# AATB-V2_1.net
KiCad netlist of a schematic drawn in Altium Designer
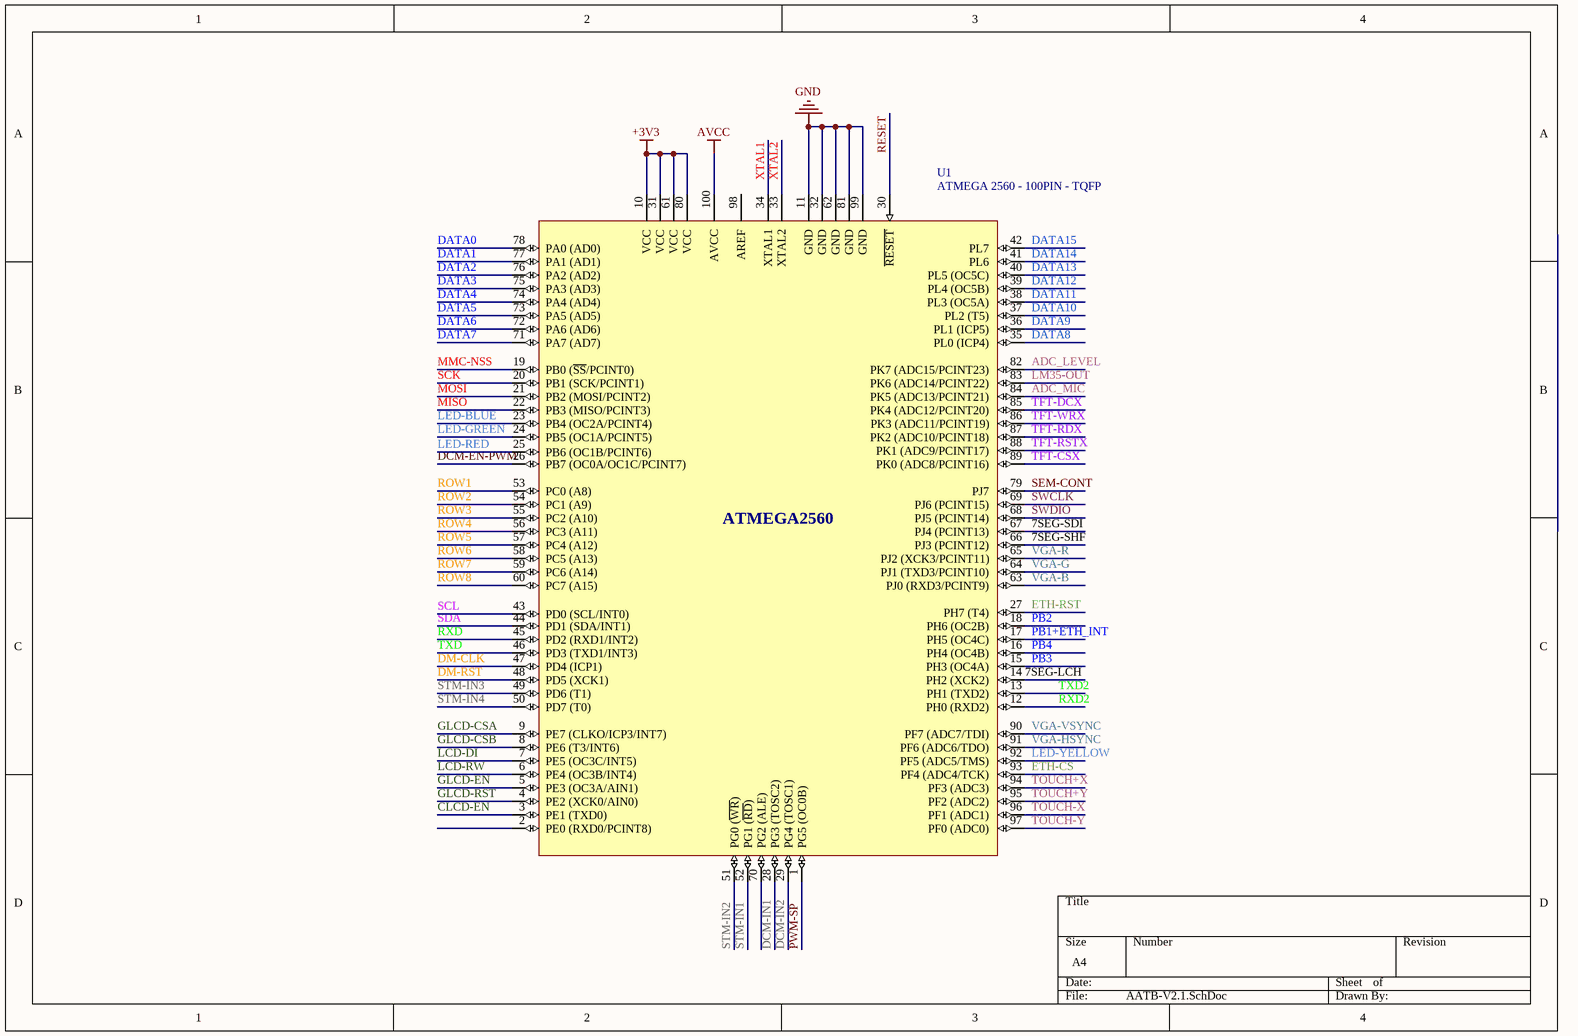
[diagram p0: AATB-V2.1.SchDoc]

(export (version "E")
  (design (tool "Eeschema 10.0.6"))
  (components
    (comp (ref "U1")
      (value "ATMEGA 2560 - 100PIN - TQFP")
      (footprint "cpu-100-26")
      (libsource (lib "Tl494") (part "ATMEGA 2560"))
    )
  )
  (nets
    (net (code "1") (name "+3V3") (class "Default")
      (node (ref "U1") (pin "10") (pinfunction "VCC_10") (pintype "power_in"))
      (node (ref "U1") (pin "31") (pinfunction "VCC_31") (pintype "power_in"))
      (node (ref "U1") (pin "61") (pinfunction "VCC_61") (pintype "power_in"))
      (node (ref "U1") (pin "80") (pinfunction "VCC_80") (pintype "power_in"))
    )
    (net (code "2") (name "/7SEG-LCH") (class "Default")
      (node (ref "U1") (pin "14") (pinfunction "PH2_(XCK2)_14") (pintype "bidirectional"))
    )
    (net (code "3") (name "/7SEG-SDI") (class "Default")
      (node (ref "U1") (pin "67") (pinfunction "PJ4_(PCINT13)_67") (pintype "bidirectional"))
    )
    (net (code "4") (name "/7SEG-SHF") (class "Default")
      (node (ref "U1") (pin "66") (pinfunction "PJ3_(PCINT12)_66") (pintype "bidirectional"))
    )
    (net (code "5") (name "/ADC_LEVEL") (class "Default")
      (node (ref "U1") (pin "82") (pinfunction "PK7_(ADC15/PCINT23)_82") (pintype "bidirectional"))
    )
    (net (code "6") (name "/ADC_MIC") (class "Default")
      (node (ref "U1") (pin "84") (pinfunction "PK5_(ADC13/PCINT21)_84") (pintype "bidirectional"))
    )
    (net (code "7") (name "/CLCD-EN") (class "Default")
      (node (ref "U1") (pin "3") (pinfunction "PE1_(TXD0)_3") (pintype "bidirectional"))
    )
    (net (code "8") (name "/DATA0") (class "Default")
      (node (ref "U1") (pin "78") (pinfunction "PA0_(AD0)_78") (pintype "bidirectional"))
    )
    (net (code "9") (name "/DATA1") (class "Default")
      (node (ref "U1") (pin "77") (pinfunction "PA1_(AD1)_77") (pintype "bidirectional"))
    )
    (net (code "10") (name "/DATA2") (class "Default")
      (node (ref "U1") (pin "76") (pinfunction "PA2_(AD2)_76") (pintype "bidirectional"))
    )
    (net (code "11") (name "/DATA3") (class "Default")
      (node (ref "U1") (pin "75") (pinfunction "PA3_(AD3)_75") (pintype "bidirectional"))
    )
    (net (code "12") (name "/DATA4") (class "Default")
      (node (ref "U1") (pin "74") (pinfunction "PA4_(AD4)_74") (pintype "bidirectional"))
    )
    (net (code "13") (name "/DATA5") (class "Default")
      (node (ref "U1") (pin "73") (pinfunction "PA5_(AD5)_73") (pintype "bidirectional"))
    )
    (net (code "14") (name "/DATA6") (class "Default")
      (node (ref "U1") (pin "72") (pinfunction "PA6_(AD6)_72") (pintype "bidirectional"))
    )
    (net (code "15") (name "/DATA7") (class "Default")
      (node (ref "U1") (pin "71") (pinfunction "PA7_(AD7)_71") (pintype "bidirectional"))
    )
    (net (code "16") (name "/DATA8") (class "Default")
      (node (ref "U1") (pin "35") (pinfunction "PL0_(ICP4)_35") (pintype "bidirectional"))
    )
    (net (code "17") (name "/DATA9") (class "Default")
      (node (ref "U1") (pin "36") (pinfunction "PL1_(ICP5)_36") (pintype "bidirectional"))
    )
    (net (code "18") (name "/DATA10") (class "Default")
      (node (ref "U1") (pin "37") (pinfunction "PL2_(T5)_37") (pintype "bidirectional"))
    )
    (net (code "19") (name "/DATA11") (class "Default")
      (node (ref "U1") (pin "38") (pinfunction "PL3_(OC5A)_38") (pintype "bidirectional"))
    )
    (net (code "20") (name "/DATA12") (class "Default")
      (node (ref "U1") (pin "39") (pinfunction "PL4_(OC5B)_39") (pintype "bidirectional"))
    )
    (net (code "21") (name "/DATA13") (class "Default")
      (node (ref "U1") (pin "40") (pinfunction "PL5_(OC5C)_40") (pintype "bidirectional"))
    )
    (net (code "22") (name "/DATA14") (class "Default")
      (node (ref "U1") (pin "41") (pinfunction "PL6_41") (pintype "bidirectional"))
    )
    (net (code "23") (name "/DATA15") (class "Default")
      (node (ref "U1") (pin "42") (pinfunction "PL7_42") (pintype "bidirectional"))
    )
    (net (code "24") (name "/DCM-EN-PWM") (class "Default")
      (node (ref "U1") (pin "26") (pinfunction "PB7_(OC0A/OC1C/PCINT7)_26") (pintype "bidirectional"))
    )
    (net (code "25") (name "/DCM-IN1") (class "Default")
      (node (ref "U1") (pin "28") (pinfunction "PG3_(TOSC2)_28") (pintype "bidirectional"))
    )
    (net (code "26") (name "/DCM-IN2") (class "Default")
      (node (ref "U1") (pin "29") (pinfunction "PG4_(TOSC1)_29") (pintype "bidirectional"))
    )
    (net (code "27") (name "/DM-CLK") (class "Default")
      (node (ref "U1") (pin "47") (pinfunction "PD4_(ICP1)_47") (pintype "bidirectional"))
    )
    (net (code "28") (name "/DM-RST") (class "Default")
      (node (ref "U1") (pin "48") (pinfunction "PD5_(XCK1)_48") (pintype "bidirectional"))
    )
    (net (code "29") (name "/ETH-CS") (class "Default")
      (node (ref "U1") (pin "93") (pinfunction "PF4_(ADC4/TCK)_93") (pintype "bidirectional"))
    )
    (net (code "30") (name "/ETH-RST") (class "Default")
      (node (ref "U1") (pin "27") (pinfunction "PH7_(T4)_27") (pintype "bidirectional"))
    )
    (net (code "31") (name "/GLCD-CSA") (class "Default")
      (node (ref "U1") (pin "9") (pinfunction "PE7_(CLKO/ICP3/INT7)_9") (pintype "bidirectional"))
    )
    (net (code "32") (name "/GLCD-CSB") (class "Default")
      (node (ref "U1") (pin "8") (pinfunction "PE6_(T3/INT6)_8") (pintype "bidirectional"))
    )
    (net (code "33") (name "/GLCD-EN") (class "Default")
      (node (ref "U1") (pin "5") (pinfunction "PE3_(OC3A/AIN1)_5") (pintype "bidirectional"))
    )
    (net (code "34") (name "/GLCD-RST") (class "Default")
      (node (ref "U1") (pin "4") (pinfunction "PE2_(XCK0/AIN0)_4") (pintype "bidirectional"))
    )
    (net (code "35") (name "/LCD-DI") (class "Default")
      (node (ref "U1") (pin "7") (pinfunction "PE5_(OC3C/INT5)_7") (pintype "bidirectional"))
    )
    (net (code "36") (name "/LCD-RW") (class "Default")
      (node (ref "U1") (pin "6") (pinfunction "PE4_(OC3B/INT4)_6") (pintype "bidirectional"))
    )
    (net (code "37") (name "/LED-BLUE") (class "Default")
      (node (ref "U1") (pin "23") (pinfunction "PB4_(OC2A/PCINT4)_23") (pintype "bidirectional"))
    )
    (net (code "38") (name "/LED-GREEN") (class "Default")
      (node (ref "U1") (pin "24") (pinfunction "PB5_(OC1A/PCINT5)_24") (pintype "bidirectional"))
    )
    (net (code "39") (name "/LED-RED") (class "Default")
      (node (ref "U1") (pin "25") (pinfunction "PB6_(OC1B/PCINT6)_25") (pintype "bidirectional"))
    )
    (net (code "40") (name "/LED-YELLOW") (class "Default")
      (node (ref "U1") (pin "92") (pinfunction "PF5_(ADC5/TMS)_92") (pintype "bidirectional"))
    )
    (net (code "41") (name "/LM35-OUT") (class "Default")
      (node (ref "U1") (pin "83") (pinfunction "PK6_(ADC14/PCINT22)_83") (pintype "bidirectional"))
    )
    (net (code "42") (name "/MISO") (class "Default")
      (node (ref "U1") (pin "22") (pinfunction "PB3_(MISO/PCINT3)_22") (pintype "bidirectional"))
    )
    (net (code "43") (name "/MMC-NSS") (class "Default")
      (node (ref "U1") (pin "19") (pinfunction "PB0_(~{SS}/PCINT0)_19") (pintype "bidirectional"))
    )
    (net (code "44") (name "/MOSI") (class "Default")
      (node (ref "U1") (pin "21") (pinfunction "PB2_(MOSI/PCINT2)_21") (pintype "bidirectional"))
    )
    (net (code "45") (name "/PB1+ETH_INT") (class "Default")
      (node (ref "U1") (pin "17") (pinfunction "PH5_(OC4C)_17") (pintype "bidirectional"))
    )
    (net (code "46") (name "/PB2") (class "Default")
      (node (ref "U1") (pin "18") (pinfunction "PH6_(OC2B)_18") (pintype "bidirectional"))
    )
    (net (code "47") (name "/PB3") (class "Default")
      (node (ref "U1") (pin "15") (pinfunction "PH3_(OC4A)_15") (pintype "bidirectional"))
    )
    (net (code "48") (name "/PB4") (class "Default")
      (node (ref "U1") (pin "16") (pinfunction "PH4_(OC4B)_16") (pintype "bidirectional"))
    )
    (net (code "49") (name "/PWM-SP") (class "Default")
      (node (ref "U1") (pin "1") (pinfunction "PG5_(OC0B)_1") (pintype "bidirectional"))
    )
    (net (code "50") (name "/RESET") (class "Default")
      (node (ref "U1") (pin "30") (pinfunction "~{RESET}_30") (pintype "input"))
    )
    (net (code "51") (name "/ROW1") (class "Default")
      (node (ref "U1") (pin "53") (pinfunction "PC0_(A8)_53") (pintype "bidirectional"))
    )
    (net (code "52") (name "/ROW2") (class "Default")
      (node (ref "U1") (pin "54") (pinfunction "PC1_(A9)_54") (pintype "bidirectional"))
    )
    (net (code "53") (name "/ROW3") (class "Default")
      (node (ref "U1") (pin "55") (pinfunction "PC2_(A10)_55") (pintype "bidirectional"))
    )
    (net (code "54") (name "/ROW4") (class "Default")
      (node (ref "U1") (pin "56") (pinfunction "PC3_(A11)_56") (pintype "bidirectional"))
    )
    (net (code "55") (name "/ROW5") (class "Default")
      (node (ref "U1") (pin "57") (pinfunction "PC4_(A12)_57") (pintype "bidirectional"))
    )
    (net (code "56") (name "/ROW6") (class "Default")
      (node (ref "U1") (pin "58") (pinfunction "PC5_(A13)_58") (pintype "bidirectional"))
    )
    (net (code "57") (name "/ROW7") (class "Default")
      (node (ref "U1") (pin "59") (pinfunction "PC6_(A14)_59") (pintype "bidirectional"))
    )
    (net (code "58") (name "/ROW8") (class "Default")
      (node (ref "U1") (pin "60") (pinfunction "PC7_(A15)_60") (pintype "bidirectional"))
    )
    (net (code "59") (name "/RXD") (class "Default")
      (node (ref "U1") (pin "45") (pinfunction "PD2_(RXD1/INT2)_45") (pintype "bidirectional"))
    )
    (net (code "60") (name "/RXD2") (class "Default")
      (node (ref "U1") (pin "12") (pinfunction "PH0_(RXD2)_12") (pintype "bidirectional"))
    )
    (net (code "61") (name "/SCK") (class "Default")
      (node (ref "U1") (pin "20") (pinfunction "PB1_(SCK/PCINT1)_20") (pintype "bidirectional"))
    )
    (net (code "62") (name "/SCL") (class "Default")
      (node (ref "U1") (pin "43") (pinfunction "PD0_(SCL/INT0)_43") (pintype "bidirectional"))
    )
    (net (code "63") (name "/SDA") (class "Default")
      (node (ref "U1") (pin "44") (pinfunction "PD1_(SDA/INT1)_44") (pintype "bidirectional"))
    )
    (net (code "64") (name "/SEM-CONT") (class "Default")
      (node (ref "U1") (pin "79") (pinfunction "PJ7_79") (pintype "bidirectional"))
    )
    (net (code "65") (name "/STM-IN1") (class "Default")
      (node (ref "U1") (pin "52") (pinfunction "PG1_(~{RD})_52") (pintype "bidirectional"))
    )
    (net (code "66") (name "/STM-IN2") (class "Default")
      (node (ref "U1") (pin "51") (pinfunction "PG0_(~{WR})_51") (pintype "bidirectional"))
    )
    (net (code "67") (name "/STM-IN3") (class "Default")
      (node (ref "U1") (pin "49") (pinfunction "PD6_(T1)_49") (pintype "bidirectional"))
    )
    (net (code "68") (name "/STM-IN4") (class "Default")
      (node (ref "U1") (pin "50") (pinfunction "PD7_(T0)_50") (pintype "bidirectional"))
    )
    (net (code "69") (name "/SWCLK") (class "Default")
      (node (ref "U1") (pin "69") (pinfunction "PJ6_(PCINT15)_69") (pintype "bidirectional"))
    )
    (net (code "70") (name "/SWDIO") (class "Default")
      (node (ref "U1") (pin "68") (pinfunction "PJ5_(PCINT14)_68") (pintype "bidirectional"))
    )
    (net (code "71") (name "/TFT-CSX") (class "Default")
      (node (ref "U1") (pin "89") (pinfunction "PK0_(ADC8/PCINT16)_89") (pintype "bidirectional"))
    )
    (net (code "72") (name "/TFT-DCX") (class "Default")
      (node (ref "U1") (pin "85") (pinfunction "PK4_(ADC12/PCINT20)_85") (pintype "bidirectional"))
    )
    (net (code "73") (name "/TFT-RDX") (class "Default")
      (node (ref "U1") (pin "87") (pinfunction "PK2_(ADC10/PCINT18)_87") (pintype "bidirectional"))
    )
    (net (code "74") (name "/TFT-RSTX") (class "Default")
      (node (ref "U1") (pin "88") (pinfunction "PK1_(ADC9/PCINT17)_88") (pintype "bidirectional"))
    )
    (net (code "75") (name "/TFT-WRX") (class "Default")
      (node (ref "U1") (pin "86") (pinfunction "PK3_(ADC11/PCINT19)_86") (pintype "bidirectional"))
    )
    (net (code "76") (name "/TOUCH+X") (class "Default")
      (node (ref "U1") (pin "94") (pinfunction "PF3_(ADC3)_94") (pintype "bidirectional"))
    )
    (net (code "77") (name "/TOUCH+Y") (class "Default")
      (node (ref "U1") (pin "95") (pinfunction "PF2_(ADC2)_95") (pintype "bidirectional"))
    )
    (net (code "78") (name "/TOUCH-X") (class "Default")
      (node (ref "U1") (pin "96") (pinfunction "PF1_(ADC1)_96") (pintype "bidirectional"))
    )
    (net (code "79") (name "/TOUCH-Y") (class "Default")
      (node (ref "U1") (pin "97") (pinfunction "PF0_(ADC0)_97") (pintype "bidirectional"))
    )
    (net (code "80") (name "/TXD") (class "Default")
      (node (ref "U1") (pin "46") (pinfunction "PD3_(TXD1/INT3)_46") (pintype "bidirectional"))
    )
    (net (code "81") (name "/TXD2") (class "Default")
      (node (ref "U1") (pin "13") (pinfunction "PH1_(TXD2)_13") (pintype "bidirectional"))
    )
    (net (code "82") (name "/VGA-B") (class "Default")
      (node (ref "U1") (pin "63") (pinfunction "PJ0_(RXD3/PCINT9)_63") (pintype "bidirectional"))
    )
    (net (code "83") (name "/VGA-G") (class "Default")
      (node (ref "U1") (pin "64") (pinfunction "PJ1_(TXD3/PCINT10)_64") (pintype "bidirectional"))
    )
    (net (code "84") (name "/VGA-HSYNC") (class "Default")
      (node (ref "U1") (pin "91") (pinfunction "PF6_(ADC6/TDO)_91") (pintype "bidirectional"))
    )
    (net (code "85") (name "/VGA-R") (class "Default")
      (node (ref "U1") (pin "65") (pinfunction "PJ2_(XCK3/PCINT11)_65") (pintype "bidirectional"))
    )
    (net (code "86") (name "/VGA-VSYNC") (class "Default")
      (node (ref "U1") (pin "90") (pinfunction "PF7_(ADC7/TDI)_90") (pintype "bidirectional"))
    )
    (net (code "87") (name "/XTAL1") (class "Default")
      (node (ref "U1") (pin "34") (pinfunction "XTAL1_34") (pintype "passive"))
    )
    (net (code "88") (name "/XTAL2") (class "Default")
      (node (ref "U1") (pin "33") (pinfunction "XTAL2_33") (pintype "passive"))
    )
    (net (code "89") (name "AVCC") (class "Default")
      (node (ref "U1") (pin "100") (pinfunction "AVCC_100") (pintype "power_in"))
    )
    (net (code "90") (name "GND") (class "Default")
      (node (ref "U1") (pin "11") (pinfunction "GND_11") (pintype "power_in"))
      (node (ref "U1") (pin "32") (pinfunction "GND_32") (pintype "power_in"))
      (node (ref "U1") (pin "62") (pinfunction "GND_62") (pintype "power_in"))
      (node (ref "U1") (pin "81") (pinfunction "GND_81") (pintype "power_in"))
      (node (ref "U1") (pin "99") (pinfunction "GND_99") (pintype "power_in"))
    )
    (net (code "91") (name "unconnected-(U1-AREF-Pad98)") (class "Default")
      (node (ref "U1") (pin "98") (pinfunction "AREF_98") (pintype "power_in"))
    )
    (net (code "92") (name "unconnected-(U1-PE0_(RXD0{slash}PCINT8)-Pad2)") (class "Default")
      (node (ref "U1") (pin "2") (pinfunction "PE0_(RXD0/PCINT8)_2") (pintype "bidirectional"))
    )
    (net (code "93") (name "unconnected-(U1-PG2_(ALE)-Pad70)") (class "Default")
      (node (ref "U1") (pin "70") (pinfunction "PG2_(ALE)_70") (pintype "bidirectional"))
    )
  )
)
